# InputConnector.net
KiCad netlist of a schematic drawn in Altium Designer
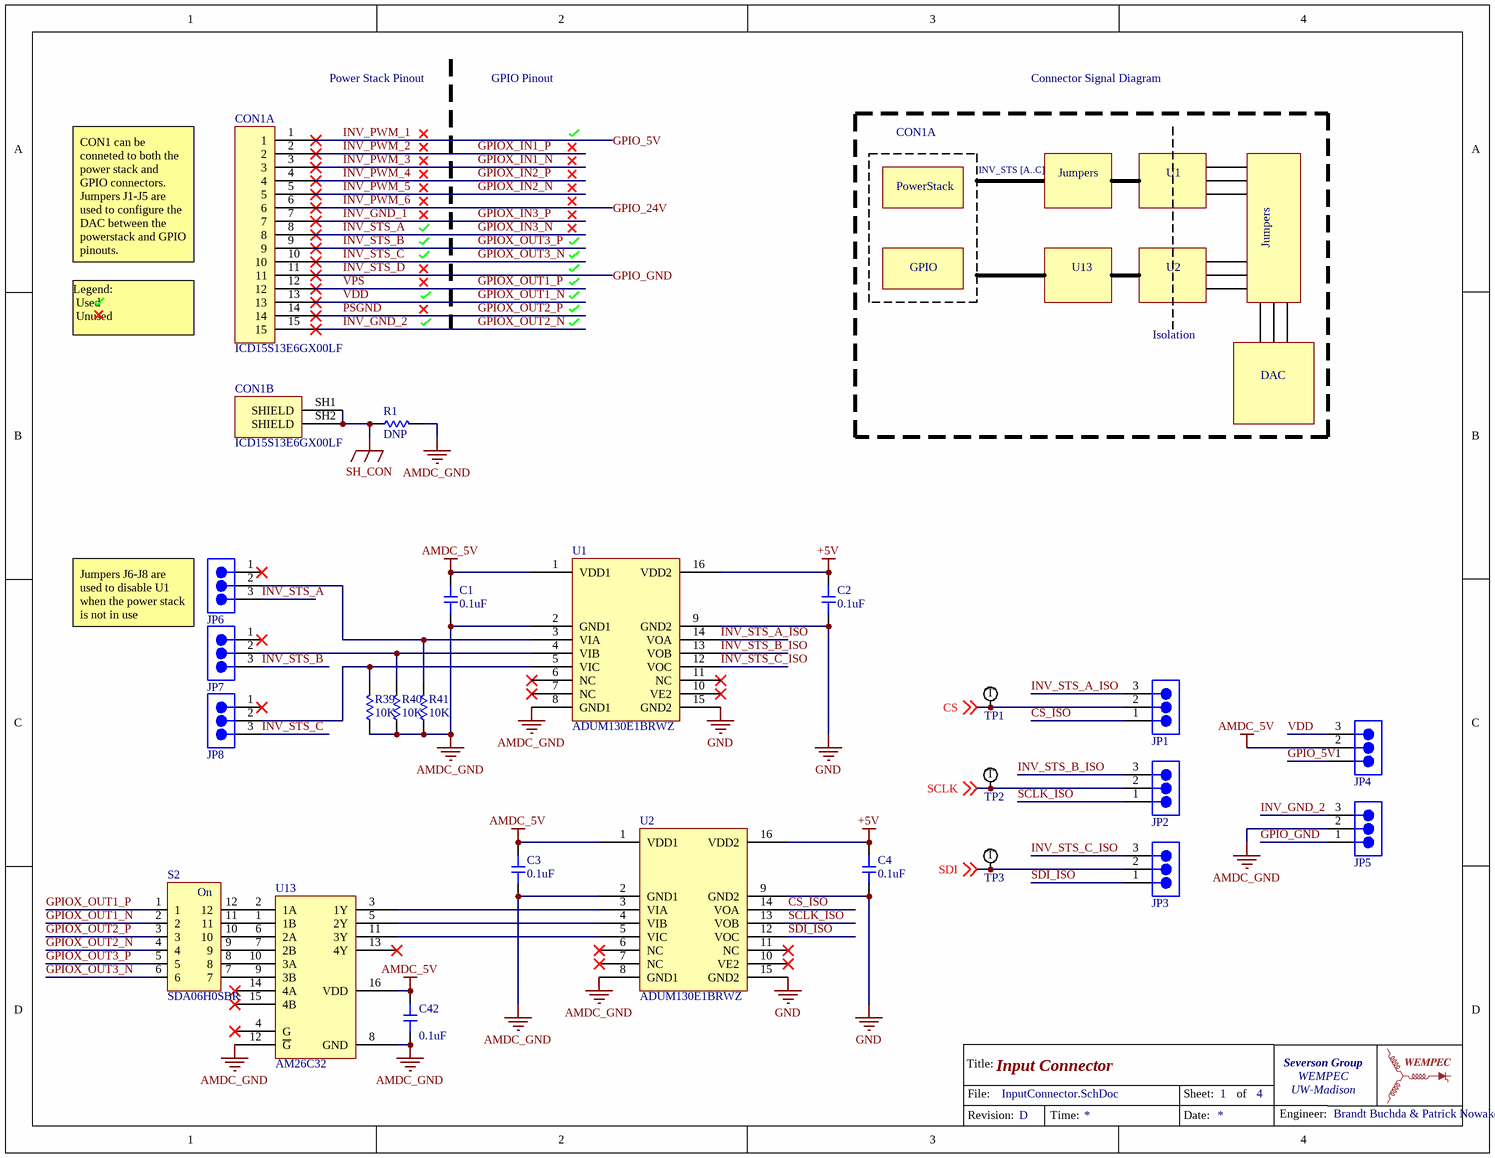
[diagram p0: InputConnector.SchDoc]

(export (version "E")
  (design (tool "Eeschema 10.0.6"))
  (components
    (comp (ref "C1")
      (value "0.1uF")
      (footprint "0603-CAP")
      (description "0.1µF ±10% 25V Ceramic Capacitor X7R 0603 (1608 Metric)")
      (fields (field (name "Comment") "CC0603KRX7R8BB104"))
      (libsource (lib "DAC") (part "Capacitor 0.1uF"))
    )
    (comp (ref "C2")
      (value "0.1uF")
      (footprint "0603-CAP")
      (description "0.1µF ±10% 25V Ceramic Capacitor X7R 0603 (1608 Metric)")
      (fields (field (name "Comment") "CC0603KRX7R8BB104"))
      (libsource (lib "DAC") (part "Capacitor 0.1uF"))
    )
    (comp (ref "C3")
      (value "0.1uF")
      (footprint "0603-CAP")
      (description "0.1µF ±10% 25V Ceramic Capacitor X7R 0603 (1608 Metric)")
      (fields (field (name "Comment") "CC0603KRX7R8BB104"))
      (libsource (lib "DAC") (part "Capacitor 0.1uF"))
    )
    (comp (ref "C4")
      (value "0.1uF")
      (footprint "0603-CAP")
      (description "0.1µF ±10% 25V Ceramic Capacitor X7R 0603 (1608 Metric)")
      (fields (field (name "Comment") "CC0603KRX7R8BB104"))
      (libsource (lib "DAC") (part "Capacitor 0.1uF"))
    )
    (comp (ref "C42")
      (value "0.1uF")
      (footprint "0603-CAP")
      (description "0.1µF ±10% 25V Ceramic Capacitor X7R 0603 (1608 Metric)")
      (fields (field (name "Comment") "CC0603KRX7R8BB104"))
      (libsource (lib "DAC") (part "Capacitor 0.1uF"))
    )
    (comp (ref "CON1")
      (value "ICD15S13E6GX00LF")
      (footprint "ICD15S13E6GX00LF")
      (description "15 Position D-Sub, High Density Receptacle, Female Sockets Connector")
      (libsource (lib "DAC") (part "ICD15S13E6GX00LF"))
    )
    (comp (ref "JP1")
      (value "TSW-103-07-F-S")
      (footprint "PIN_HEADER_1X3")
      (description "Connector Header Through Hole 3 position 0.100\" (2.54mm)")
      (libsource (lib "DAC") (part "TSW-103-07-F-S"))
    )
    (comp (ref "JP2")
      (value "TSW-103-07-F-S")
      (footprint "PIN_HEADER_1X3")
      (description "Connector Header Through Hole 3 position 0.100\" (2.54mm)")
      (libsource (lib "DAC") (part "TSW-103-07-F-S"))
    )
    (comp (ref "JP3")
      (value "TSW-103-07-F-S")
      (footprint "PIN_HEADER_1X3")
      (description "Connector Header Through Hole 3 position 0.100\" (2.54mm)")
      (libsource (lib "DAC") (part "TSW-103-07-F-S"))
    )
    (comp (ref "JP4")
      (value "TSW-103-07-F-S")
      (footprint "PIN_HEADER_1X3")
      (description "Connector Header Through Hole 3 position 0.100\" (2.54mm)")
      (libsource (lib "DAC") (part "TSW-103-07-F-S"))
    )
    (comp (ref "JP5")
      (value "TSW-103-07-F-S")
      (footprint "PIN_HEADER_1X3")
      (description "Connector Header Through Hole 3 position 0.100\" (2.54mm)")
      (libsource (lib "DAC") (part "TSW-103-07-F-S"))
    )
    (comp (ref "JP6")
      (value "TSW-103-07-F-S")
      (footprint "PIN_HEADER_1X3")
      (description "Connector Header Through Hole 3 position 0.100\" (2.54mm)")
      (libsource (lib "DAC") (part "TSW-103-07-F-S"))
    )
    (comp (ref "JP7")
      (value "TSW-103-07-F-S")
      (footprint "PIN_HEADER_1X3")
      (description "Connector Header Through Hole 3 position 0.100\" (2.54mm)")
      (libsource (lib "DAC") (part "TSW-103-07-F-S"))
    )
    (comp (ref "JP8")
      (value "TSW-103-07-F-S")
      (footprint "PIN_HEADER_1X3")
      (description "Connector Header Through Hole 3 position 0.100\" (2.54mm)")
      (libsource (lib "DAC") (part "TSW-103-07-F-S"))
    )
    (comp (ref "R1")
      (value "DNP")
      (footprint "0603-RES")
      (fields (field (name "Comment") "Resistor"))
      (libsource (lib "DAC") (part "Resistor"))
    )
    (comp (ref "R39")
      (value "10K")
      (footprint "0603-RES")
      (fields (field (name "Comment") "ERJ-PB3B1002V"))
      (libsource (lib "DAC") (part "Resistor 10K"))
    )
    (comp (ref "R40")
      (value "10K")
      (footprint "0603-RES")
      (fields (field (name "Comment") "ERJ-PB3B1002V"))
      (libsource (lib "DAC") (part "Resistor 10K"))
    )
    (comp (ref "R41")
      (value "10K")
      (footprint "0603-RES")
      (fields (field (name "Comment") "ERJ-PB3B1002V"))
      (libsource (lib "DAC") (part "Resistor 10K"))
    )
    (comp (ref "S2")
      (value "SDA06H0SBR")
      (footprint "DAC:SDA06H0SBR")
      (description "SWITCH SLIDE DIP SPST 25MA 24V")
      (libsource (lib "DAC") (part "SDA06H0SBR"))
    )
    (comp (ref "TP1") (value "Test Point") (footprint "RCU-0C") (libsource (lib "DAC") (part "Test Point")))
    (comp (ref "TP2") (value "Test Point") (footprint "RCU-0C") (libsource (lib "DAC") (part "Test Point")))
    (comp (ref "TP3") (value "Test Point") (footprint "RCU-0C") (libsource (lib "DAC") (part "Test Point")))
    (comp (ref "U1")
      (value "ADUM130E1BRWZ")
      (footprint "SOIC127P1030X265-16N")
      (libsource (lib "DAC") (part "ADUM130E1BRWZ"))
    )
    (comp (ref "U2")
      (value "ADUM130E1BRWZ")
      (footprint "SOIC127P1030X265-16N")
      (libsource (lib "DAC") (part "ADUM130E1BRWZ"))
    )
    (comp (ref "U13")
      (value "AM26C32")
      (footprint "TSOP65P640X120-16N")
      (description "IC RCVR RS422 QUAD DIFF 16TSSOP")
      (libsource (lib "DAC") (part "AM26C32"))
    )
  )
  (nets
    (net (code "1") (name "+5V") (class "Default")
      (node (ref "C2") (pin "2") (pinfunction "2_2") (pintype "passive"))
      (node (ref "C4") (pin "2") (pinfunction "2_2") (pintype "passive"))
      (node (ref "U1") (pin "16") (pinfunction "VDD2_16") (pintype "passive"))
      (node (ref "U2") (pin "16") (pinfunction "VDD2_16") (pintype "passive"))
    )
    (net (code "2") (name "/CS_ISO") (class "Default")
      (node (ref "JP1") (pin "1") (pinfunction "76_1") (pintype "passive"))
      (node (ref "U2") (pin "14") (pinfunction "VOA_14") (pintype "passive"))
    )
    (net (code "3") (name "/GPIOX_IN1_N") (class "Default")
      (node (ref "CON1") (pin "3") (pinfunction "3_3") (pintype "passive+no_connect"))
    )
    (net (code "4") (name "/GPIOX_IN1_P") (class "Default")
      (node (ref "CON1") (pin "2") (pinfunction "2_2") (pintype "passive+no_connect"))
    )
    (net (code "5") (name "/GPIOX_IN2_N") (class "Default")
      (node (ref "CON1") (pin "5") (pinfunction "5_5") (pintype "passive+no_connect"))
    )
    (net (code "6") (name "/GPIOX_IN2_P") (class "Default")
      (node (ref "CON1") (pin "4") (pinfunction "4_4") (pintype "passive+no_connect"))
    )
    (net (code "7") (name "/GPIOX_IN3_N") (class "Default")
      (node (ref "CON1") (pin "8") (pinfunction "8_8") (pintype "passive"))
      (node (ref "JP6") (pin "3") (pinfunction "75_3") (pintype "passive"))
    )
    (net (code "8") (name "/GPIOX_IN3_P") (class "Default")
      (node (ref "CON1") (pin "7") (pinfunction "7_7") (pintype "passive+no_connect"))
    )
    (net (code "9") (name "/GPIOX_OUT1_N") (class "Default")
      (node (ref "CON1") (pin "13") (pinfunction "13_13") (pintype "passive"))
      (node (ref "JP4") (pin "3") (pinfunction "75_3") (pintype "passive"))
      (node (ref "S2") (pin "2") (pinfunction "2_2") (pintype "passive"))
    )
    (net (code "10") (name "/GPIOX_OUT1_P") (class "Default")
      (node (ref "CON1") (pin "12") (pinfunction "12_12") (pintype "passive"))
      (node (ref "S2") (pin "1") (pinfunction "1_1") (pintype "passive"))
    )
    (net (code "11") (name "/GPIOX_OUT2_N") (class "Default")
      (node (ref "CON1") (pin "15") (pinfunction "15_15") (pintype "passive"))
      (node (ref "JP5") (pin "3") (pinfunction "75_3") (pintype "passive"))
      (node (ref "S2") (pin "4") (pinfunction "4_4") (pintype "passive"))
    )
    (net (code "12") (name "/GPIOX_OUT2_P") (class "Default")
      (node (ref "CON1") (pin "14") (pinfunction "14_14") (pintype "passive"))
      (node (ref "S2") (pin "3") (pinfunction "3_3") (pintype "passive"))
    )
    (net (code "13") (name "/GPIOX_OUT3_N") (class "Default")
      (node (ref "CON1") (pin "10") (pinfunction "10_10") (pintype "passive"))
      (node (ref "JP8") (pin "3") (pinfunction "75_3") (pintype "passive"))
      (node (ref "S2") (pin "6") (pinfunction "6_6") (pintype "passive"))
    )
    (net (code "14") (name "/GPIOX_OUT3_P") (class "Default")
      (node (ref "CON1") (pin "9") (pinfunction "9_9") (pintype "passive"))
      (node (ref "JP7") (pin "3") (pinfunction "75_3") (pintype "passive"))
      (node (ref "S2") (pin "5") (pinfunction "5_5") (pintype "passive"))
    )
    (net (code "15") (name "/GPIO_5V") (class "Default")
      (node (ref "CON1") (pin "1") (pinfunction "1_1") (pintype "passive"))
      (node (ref "JP4") (pin "1") (pinfunction "76_1") (pintype "passive"))
    )
    (net (code "16") (name "/GPIO_24V") (class "Default")
      (node (ref "CON1") (pin "6") (pinfunction "6_6") (pintype "passive+no_connect"))
    )
    (net (code "17") (name "/GPIO_GND") (class "Default")
      (node (ref "CON1") (pin "11") (pinfunction "11_11") (pintype "passive"))
      (node (ref "JP5") (pin "1") (pinfunction "76_1") (pintype "passive"))
    )
    (net (code "18") (name "/INV_STS_A_ISO") (class "Default")
      (node (ref "JP1") (pin "3") (pinfunction "75_3") (pintype "passive"))
      (node (ref "U1") (pin "14") (pinfunction "VOA_14") (pintype "passive"))
    )
    (net (code "19") (name "/INV_STS_B_ISO") (class "Default")
      (node (ref "JP2") (pin "3") (pinfunction "75_3") (pintype "passive"))
      (node (ref "U1") (pin "13") (pinfunction "VOB_13") (pintype "passive"))
    )
    (net (code "20") (name "/INV_STS_C_ISO") (class "Default")
      (node (ref "JP3") (pin "3") (pinfunction "75_3") (pintype "passive"))
      (node (ref "U1") (pin "12") (pinfunction "VOC_12") (pintype "passive"))
    )
    (net (code "21") (name "/SCLK_ISO") (class "Default")
      (node (ref "JP2") (pin "1") (pinfunction "76_1") (pintype "passive"))
      (node (ref "U2") (pin "13") (pinfunction "VOB_13") (pintype "passive"))
    )
    (net (code "22") (name "/SDI_ISO") (class "Default")
      (node (ref "JP3") (pin "1") (pinfunction "76_1") (pintype "passive"))
      (node (ref "U2") (pin "12") (pinfunction "VOC_12") (pintype "passive"))
    )
    (net (code "23") (name "AMDC_5V") (class "Default")
      (node (ref "C1") (pin "2") (pinfunction "2_2") (pintype "passive"))
      (node (ref "C3") (pin "2") (pinfunction "2_2") (pintype "passive"))
      (node (ref "C42") (pin "2") (pinfunction "2_2") (pintype "passive"))
      (node (ref "JP4") (pin "2") (pinfunction "75_2") (pintype "passive"))
      (node (ref "U1") (pin "1") (pinfunction "VDD1_1") (pintype "passive"))
      (node (ref "U13") (pin "16") (pinfunction "VDD_16") (pintype "passive"))
      (node (ref "U2") (pin "1") (pinfunction "VDD1_1") (pintype "passive"))
    )
    (net (code "24") (name "AMDC_GND") (class "Default")
      (node (ref "C1") (pin "1") (pinfunction "1_1") (pintype "passive"))
      (node (ref "C3") (pin "1") (pinfunction "1_1") (pintype "passive"))
      (node (ref "C42") (pin "1") (pinfunction "1_1") (pintype "passive"))
      (node (ref "JP5") (pin "2") (pinfunction "75_2") (pintype "passive"))
      (node (ref "R1") (pin "2") (pinfunction "2_2") (pintype "passive"))
      (node (ref "R39") (pin "1") (pinfunction "1_1") (pintype "passive"))
      (node (ref "R40") (pin "1") (pinfunction "1_1") (pintype "passive"))
      (node (ref "R41") (pin "1") (pinfunction "1_1") (pintype "passive"))
      (node (ref "U1") (pin "2") (pinfunction "GND1_2") (pintype "passive"))
      (node (ref "U1") (pin "8") (pinfunction "GND1_8") (pintype "passive"))
      (node (ref "U13") (pin "12") (pinfunction "~{G}_12") (pintype "passive"))
      (node (ref "U13") (pin "8") (pinfunction "GND_8") (pintype "passive"))
      (node (ref "U2") (pin "2") (pinfunction "GND1_2") (pintype "passive"))
      (node (ref "U2") (pin "8") (pinfunction "GND1_8") (pintype "passive"))
    )
    (net (code "25") (name "CS") (class "Default")
      (node (ref "JP1") (pin "2") (pinfunction "75_2") (pintype "passive"))
      (node (ref "TP1") (pin "1") (pinfunction "1_1") (pintype "passive"))
    )
    (net (code "26") (name "GND") (class "Default")
      (node (ref "C2") (pin "1") (pinfunction "1_1") (pintype "passive"))
      (node (ref "C4") (pin "1") (pinfunction "1_1") (pintype "passive"))
      (node (ref "U1") (pin "15") (pinfunction "GND2_15") (pintype "passive"))
      (node (ref "U1") (pin "9") (pinfunction "GND2_9") (pintype "passive"))
      (node (ref "U2") (pin "15") (pinfunction "GND2_15") (pintype "passive"))
      (node (ref "U2") (pin "9") (pinfunction "GND2_9") (pintype "passive"))
    )
    (net (code "27") (name "Net-(U1-VIA)") (class "Default")
      (node (ref "JP6") (pin "2") (pinfunction "75_2") (pintype "passive"))
      (node (ref "R41") (pin "2") (pinfunction "2_2") (pintype "passive"))
      (node (ref "U1") (pin "3") (pinfunction "VIA_3") (pintype "passive"))
    )
    (net (code "28") (name "Net-(U1-VIB)") (class "Default")
      (node (ref "JP7") (pin "2") (pinfunction "75_2") (pintype "passive"))
      (node (ref "R40") (pin "2") (pinfunction "2_2") (pintype "passive"))
      (node (ref "U1") (pin "4") (pinfunction "VIB_4") (pintype "passive"))
    )
    (net (code "29") (name "Net-(U1-VIC)") (class "Default")
      (node (ref "JP8") (pin "2") (pinfunction "75_2") (pintype "passive"))
      (node (ref "R39") (pin "2") (pinfunction "2_2") (pintype "passive"))
      (node (ref "U1") (pin "5") (pinfunction "VIC_5") (pintype "passive"))
    )
    (net (code "30") (name "Net-(U13-1A)") (class "Default")
      (node (ref "S2") (pin "12") (pinfunction "12_12") (pintype "passive"))
      (node (ref "U13") (pin "2") (pinfunction "1A_2") (pintype "passive"))
    )
    (net (code "31") (name "Net-(U13-1B)") (class "Default")
      (node (ref "S2") (pin "11") (pinfunction "11_11") (pintype "passive"))
      (node (ref "U13") (pin "1") (pinfunction "1B_1") (pintype "passive"))
    )
    (net (code "32") (name "Net-(U13-1Y)") (class "Default")
      (node (ref "U13") (pin "3") (pinfunction "1Y_3") (pintype "passive"))
      (node (ref "U2") (pin "3") (pinfunction "VIA_3") (pintype "passive"))
    )
    (net (code "33") (name "Net-(U13-2A)") (class "Default")
      (node (ref "S2") (pin "10") (pinfunction "10_10") (pintype "passive"))
      (node (ref "U13") (pin "6") (pinfunction "2A_6") (pintype "passive"))
    )
    (net (code "34") (name "Net-(U13-2B)") (class "Default")
      (node (ref "S2") (pin "9") (pinfunction "9_9") (pintype "passive"))
      (node (ref "U13") (pin "7") (pinfunction "2B_7") (pintype "passive"))
    )
    (net (code "35") (name "Net-(U13-2Y)") (class "Default")
      (node (ref "U13") (pin "5") (pinfunction "2Y_5") (pintype "passive"))
      (node (ref "U2") (pin "4") (pinfunction "VIB_4") (pintype "passive"))
    )
    (net (code "36") (name "Net-(U13-3A)") (class "Default")
      (node (ref "S2") (pin "8") (pinfunction "8_8") (pintype "passive"))
      (node (ref "U13") (pin "10") (pinfunction "3A_10") (pintype "passive"))
    )
    (net (code "37") (name "Net-(U13-3B)") (class "Default")
      (node (ref "S2") (pin "7") (pinfunction "7_7") (pintype "passive"))
      (node (ref "U13") (pin "9") (pinfunction "3B_9") (pintype "passive"))
    )
    (net (code "38") (name "Net-(U13-3Y)") (class "Default")
      (node (ref "U13") (pin "11") (pinfunction "3Y_11") (pintype "passive"))
      (node (ref "U2") (pin "5") (pinfunction "VIC_5") (pintype "passive"))
    )
    (net (code "39") (name "SCLK") (class "Default")
      (node (ref "JP2") (pin "2") (pinfunction "75_2") (pintype "passive"))
      (node (ref "TP2") (pin "1") (pinfunction "1_1") (pintype "passive"))
    )
    (net (code "40") (name "SDI") (class "Default")
      (node (ref "JP3") (pin "2") (pinfunction "75_2") (pintype "passive"))
      (node (ref "TP3") (pin "1") (pinfunction "1_1") (pintype "passive"))
    )
    (net (code "41") (name "SH_CON") (class "Default")
      (node (ref "CON1") (pin "SH1") (pinfunction "SHIELD_SH1") (pintype "passive"))
      (node (ref "CON1") (pin "SH2") (pinfunction "SHIELD_SH2") (pintype "passive"))
      (node (ref "R1") (pin "1") (pinfunction "1_1") (pintype "passive"))
    )
    (net (code "42") (name "unconnected-(JP6-76-Pad1)") (class "Default")
      (node (ref "JP6") (pin "1") (pinfunction "76_1") (pintype "passive+no_connect"))
    )
    (net (code "43") (name "unconnected-(JP7-76-Pad1)") (class "Default")
      (node (ref "JP7") (pin "1") (pinfunction "76_1") (pintype "passive+no_connect"))
    )
    (net (code "44") (name "unconnected-(JP8-76-Pad1)") (class "Default")
      (node (ref "JP8") (pin "1") (pinfunction "76_1") (pintype "passive+no_connect"))
    )
    (net (code "45") (name "unconnected-(U1-NC-Pad6)") (class "Default")
      (node (ref "U1") (pin "6") (pinfunction "NC_6") (pintype "passive+no_connect"))
    )
    (net (code "46") (name "unconnected-(U1-NC-Pad7)") (class "Default")
      (node (ref "U1") (pin "7") (pinfunction "NC_7") (pintype "passive+no_connect"))
    )
    (net (code "47") (name "unconnected-(U1-NC-Pad11)") (class "Default")
      (node (ref "U1") (pin "11") (pinfunction "NC_11") (pintype "passive+no_connect"))
    )
    (net (code "48") (name "unconnected-(U1-VE2-Pad10)") (class "Default")
      (node (ref "U1") (pin "10") (pinfunction "VE2_10") (pintype "passive+no_connect"))
    )
    (net (code "49") (name "unconnected-(U2-NC-Pad6)") (class "Default")
      (node (ref "U2") (pin "6") (pinfunction "NC_6") (pintype "passive+no_connect"))
    )
    (net (code "50") (name "unconnected-(U2-NC-Pad7)") (class "Default")
      (node (ref "U2") (pin "7") (pinfunction "NC_7") (pintype "passive+no_connect"))
    )
    (net (code "51") (name "unconnected-(U2-NC-Pad11)") (class "Default")
      (node (ref "U2") (pin "11") (pinfunction "NC_11") (pintype "passive+no_connect"))
    )
    (net (code "52") (name "unconnected-(U2-VE2-Pad10)") (class "Default")
      (node (ref "U2") (pin "10") (pinfunction "VE2_10") (pintype "passive+no_connect"))
    )
    (net (code "53") (name "unconnected-(U13-4A-Pad14)") (class "Default")
      (node (ref "U13") (pin "14") (pinfunction "4A_14") (pintype "passive+no_connect"))
    )
    (net (code "54") (name "unconnected-(U13-4B-Pad15)") (class "Default")
      (node (ref "U13") (pin "15") (pinfunction "4B_15") (pintype "passive+no_connect"))
    )
    (net (code "55") (name "unconnected-(U13-4Y-Pad13)") (class "Default")
      (node (ref "U13") (pin "13") (pinfunction "4Y_13") (pintype "passive+no_connect"))
    )
    (net (code "56") (name "unconnected-(U13-G-Pad4)") (class "Default")
      (node (ref "U13") (pin "4") (pinfunction "G_4") (pintype "passive+no_connect"))
    )
  )
)
